# triger.net
KiCad netlist of a schematic drawn in Altium Designer
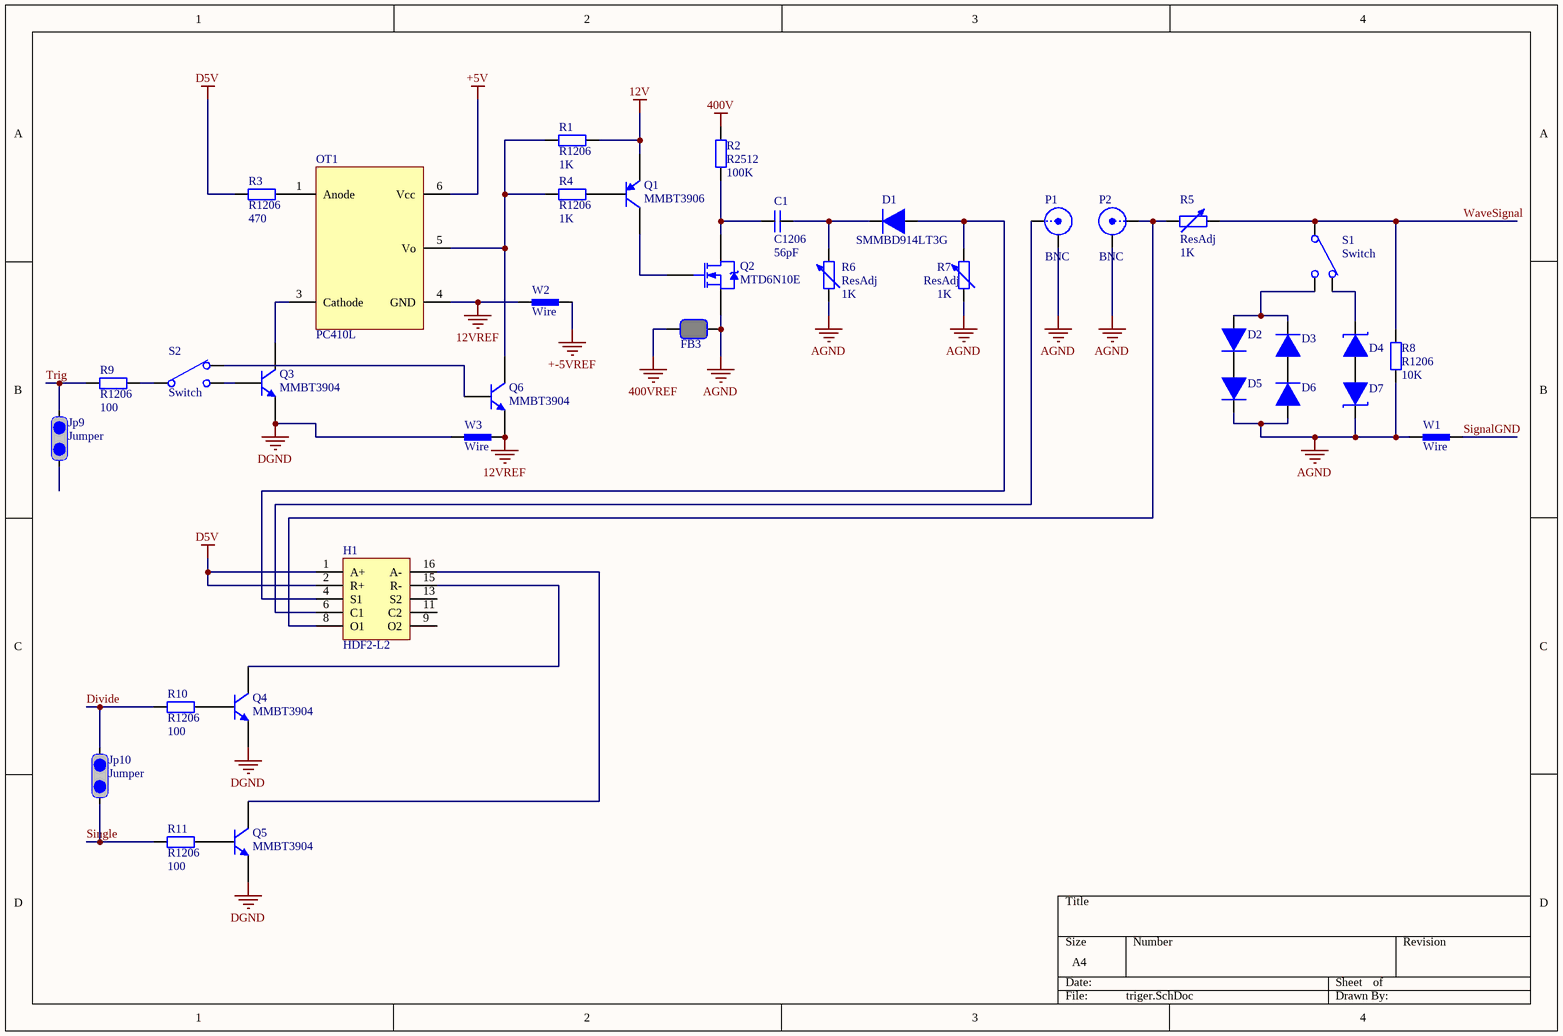
[diagram p0: triger.SchDoc]

(export (version "E")
  (design (tool "Eeschema 10.0.6"))
  (components
    (comp (ref "C1")
      (value "C1206")
      (footprint "1206")
      (description "Capacitor, 1206")
      (fields (field (name "ALTIUM_VALUE") "56pF"))
      (libsource (lib "UFDLib") (part "C1206"))
    )
    (comp (ref "D1")
      (value "SMMBD914LT3G")
      (footprint "SMMBD914LT3G")
      (description "Switching Diode")
      (libsource (lib "UFDLib") (part "SMMBD914LT3G"))
    )
    (comp (ref "D2")
      (value "SMMBD914LT3G")
      (footprint "SMMBD914LT3G")
      (description "Switching Diode")
      (libsource (lib "UFDLib") (part "SMMBD914LT3G"))
    )
    (comp (ref "D3")
      (value "SMMBD914LT3G")
      (footprint "SMMBD914LT3G")
      (description "Switching Diode")
      (libsource (lib "UFDLib") (part "SMMBD914LT3G"))
    )
    (comp (ref "D4")
      (value "ZMM2V4")
      (footprint "DIODE1206")
      (description "Voltage Stabilizing Diode, 2.4V")
      (libsource (lib "UFDLib") (part "ZMM2V4"))
    )
    (comp (ref "D5")
      (value "SMMBD914LT3G")
      (footprint "SMMBD914LT3G")
      (description "Switching Diode")
      (libsource (lib "UFDLib") (part "SMMBD914LT3G"))
    )
    (comp (ref "D6")
      (value "SMMBD914LT3G")
      (footprint "SMMBD914LT3G")
      (description "Switching Diode")
      (libsource (lib "UFDLib") (part "SMMBD914LT3G"))
    )
    (comp (ref "D7")
      (value "ZMM2V4")
      (footprint "DIODE1206")
      (description "Voltage Stabilizing Diode, 2.4V")
      (libsource (lib "UFDLib") (part "ZMM2V4"))
    )
    (comp (ref "FB3")
      (value "FB0805")
      (footprint "0805")
      (description "Chip Bead, 0805")
      (libsource (lib "UFDLib") (part "FB0805"))
    )
    (comp (ref "H1")
      (value "HDF2-L2")
      (footprint "RELAY-HFD2-L2")
      (description "Relay, HDF2-XX-XX-L2-XX")
      (libsource (lib "UFDLib") (part "Relay-HDF2-L2"))
    )
    (comp (ref "Jp9") (value "Jumper") (footprint "JUMPER") (libsource (lib "UFDLib") (part "Jumper")))
    (comp (ref "Jp10") (value "Jumper") (footprint "JUMPER") (libsource (lib "UFDLib") (part "Jumper")))
    (comp (ref "OT1") (value "PC410L") (footprint "SOP5") (libsource (lib "UFDLib") (part "PC410L")))
    (comp (ref "P1")
      (value "BNC")
      (footprint "BNC_RA CON")
      (description "BNC Elbow Connector")
      (fields (field (name "PUBLISHER") "Altium Limited"))
      (libsource (lib "Miscellaneous Connectors") (part "BNC"))
    )
    (comp (ref "P2")
      (value "BNC")
      (footprint "BNC_RA CON")
      (description "BNC Elbow Connector")
      (fields (field (name "PUBLISHER") "Altium Limited"))
      (libsource (lib "Miscellaneous Connectors") (part "BNC"))
    )
    (comp (ref "Q1")
      (value "MMBT3906")
      (footprint "SOT23_M")
      (description "PNP Switching Transistor")
      (fields (field (name "PUBLISHER") "Altium Limited"))
      (libsource (lib "Philips Discrete BJT - Low Power") (part "MMBT3906"))
    )
    (comp (ref "Q2")
      (value "MTD6N10E")
      (footprint "369A-13")
      (description "TMOS E-FET Power Field Effect Transistor DPAK for Surface Mount")
      (fields (field (name "PUBLISHER") "Altium Limited"))
      (libsource (lib "Motorola Discrete MOSFET") (part "MTD6N10E"))
    )
    (comp (ref "Q3")
      (value "MMBT3904")
      (footprint "SOT23_M")
      (description "NPN Switching Transistor")
      (fields (field (name "PUBLISHER") "Altium Limited"))
      (libsource (lib "Philips Discrete BJT - Low Power") (part "MMBT3904"))
    )
    (comp (ref "Q4")
      (value "MMBT3904")
      (footprint "SOT23_M")
      (description "NPN Switching Transistor")
      (fields (field (name "PUBLISHER") "Altium Limited"))
      (libsource (lib "Philips Discrete BJT - Low Power") (part "MMBT3904"))
    )
    (comp (ref "Q5")
      (value "MMBT3904")
      (footprint "SOT23_M")
      (description "NPN Switching Transistor")
      (fields (field (name "PUBLISHER") "Altium Limited"))
      (libsource (lib "Philips Discrete BJT - Low Power") (part "MMBT3904"))
    )
    (comp (ref "Q6")
      (value "MMBT3904")
      (footprint "SOT23_M")
      (description "NPN Switching Transistor")
      (fields (field (name "PUBLISHER") "Altium Limited"))
      (libsource (lib "Philips Discrete BJT - Low Power") (part "MMBT3904"))
    )
    (comp (ref "R1")
      (value "R1206")
      (footprint "1206")
      (description "Resistor, 1206, 1/4W")
      (fields (field (name "ALTIUM_VALUE") "1K"))
      (libsource (lib "UFDLib") (part "R1206"))
    )
    (comp (ref "R2")
      (value "R2512")
      (footprint "2512")
      (description "Resistor, 2512, 1W")
      (fields (field (name "ALTIUM_VALUE") "100K"))
      (libsource (lib "UFDLib") (part "R2512"))
    )
    (comp (ref "R3")
      (value "R1206")
      (footprint "1206")
      (description "Resistor, 1206, 1/4W")
      (fields (field (name "ALTIUM_VALUE") "470"))
      (libsource (lib "UFDLib") (part "R1206"))
    )
    (comp (ref "R4")
      (value "R1206")
      (footprint "1206")
      (description "Resistor, 1206, 1/4W")
      (fields (field (name "ALTIUM_VALUE") "1K"))
      (libsource (lib "UFDLib") (part "R1206"))
    )
    (comp (ref "R5")
      (value "ResAdj")
      (footprint "Adjust Resistor")
      (description "Adjustable Resistor")
      (fields (field (name "ALTIUM_VALUE") "1K"))
      (libsource (lib "UFDLib") (part "ResAdj"))
    )
    (comp (ref "R6")
      (value "ResAdj")
      (footprint "Adjust Resistor")
      (description "Adjustable Resistor")
      (fields (field (name "ALTIUM_VALUE") "1K"))
      (libsource (lib "") (part "ResAdj_1"))
    )
    (comp (ref "R7")
      (value "ResAdj")
      (footprint "Adjust Resistor")
      (description "Adjustable Resistor")
      (fields (field (name "ALTIUM_VALUE") "1K"))
      (libsource (lib "") (part "ResAdj_1"))
    )
    (comp (ref "R8")
      (value "R1206")
      (footprint "1206")
      (description "Resistor, 1206, 1/4W")
      (fields (field (name "ALTIUM_VALUE") "10K"))
      (libsource (lib "") (part "R1206_1"))
    )
    (comp (ref "R9")
      (value "R1206")
      (footprint "1206")
      (description "Resistor, 1206, 1/4W")
      (fields (field (name "ALTIUM_VALUE") "100"))
      (libsource (lib "UFDLib") (part "R1206"))
    )
    (comp (ref "R10")
      (value "R1206")
      (footprint "1206")
      (description "Resistor, 1206, 1/4W")
      (fields (field (name "ALTIUM_VALUE") "100"))
      (libsource (lib "UFDLib") (part "R1206"))
    )
    (comp (ref "R11")
      (value "R1206")
      (footprint "1206")
      (description "Resistor, 1206, 1/4W")
      (fields (field (name "ALTIUM_VALUE") "100"))
      (libsource (lib "UFDLib") (part "R1206"))
    )
    (comp (ref "S1")
      (value "Switch")
      (footprint "MSS-22C02")
      (description "Duble Switch")
      (libsource (lib "UFDLib") (part "MSS-22C02"))
    )
    (comp (ref "S2")
      (value "Switch")
      (footprint "MSS-22C02")
      (description "Duble Switch")
      (libsource (lib "UFDLib") (part "MSS-22C02"))
    )
    (comp (ref "W1") (value "Wire") (footprint "WIRE") (libsource (lib "UFDLib") (part "Wire")))
    (comp (ref "W2") (value "Wire") (footprint "WIRE") (libsource (lib "UFDLib") (part "Wire")))
    (comp (ref "W3") (value "Wire") (footprint "WIRE") (libsource (lib "UFDLib") (part "Wire")))
  )
  (nets
    (net (code "1") (name "+-5VREF") (class "Default")
      (node (ref "W2") (pin "2") (pinfunction "b_2") (pintype "passive"))
    )
    (net (code "2") (name "+5V") (class "Default")
      (node (ref "OT1") (pin "6") (pinfunction "Vcc_6") (pintype "passive"))
    )
    (net (code "3") (name "/Divide") (class "Default")
      (node (ref "Jp10") (pin "2") (pinfunction "b_2") (pintype "passive"))
      (node (ref "R10") (pin "1") (pinfunction "a_1") (pintype "passive"))
    )
    (net (code "4") (name "/SignalGND") (class "Default")
      (node (ref "W1") (pin "2") (pinfunction "b_2") (pintype "passive"))
    )
    (net (code "5") (name "/Single") (class "Default")
      (node (ref "Jp10") (pin "1") (pinfunction "a_1") (pintype "passive"))
      (node (ref "R11") (pin "1") (pinfunction "a_1") (pintype "passive"))
    )
    (net (code "6") (name "/Trig") (class "Default")
      (node (ref "Jp9") (pin "2") (pinfunction "b_2") (pintype "passive"))
      (node (ref "R9") (pin "1") (pinfunction "a_1") (pintype "passive"))
    )
    (net (code "7") (name "/WaveSignal") (class "Default")
      (node (ref "R5") (pin "b") (pinfunction "b_b") (pintype "passive"))
      (node (ref "R8") (pin "2") (pinfunction "b_2") (pintype "passive"))
      (node (ref "S1") (pin "a") (pinfunction "a_a") (pintype "passive"))
    )
    (net (code "8") (name "12V") (class "Default")
      (node (ref "Q1") (pin "2") (pinfunction "E_2") (pintype "passive"))
      (node (ref "R1") (pin "2") (pinfunction "b_2") (pintype "passive"))
    )
    (net (code "9") (name "12VREF") (class "Default")
      (node (ref "OT1") (pin "4") (pinfunction "GND_4") (pintype "passive"))
      (node (ref "Q6") (pin "2") (pinfunction "E_2") (pintype "passive"))
      (node (ref "W2") (pin "1") (pinfunction "a_1") (pintype "passive"))
      (node (ref "W3") (pin "2") (pinfunction "b_2") (pintype "passive"))
    )
    (net (code "10") (name "400V") (class "Default")
      (node (ref "R2") (pin "2") (pinfunction "b_2") (pintype "passive"))
    )
    (net (code "11") (name "400VREF") (class "Default")
      (node (ref "FB3") (pin "2") (pinfunction "b_2") (pintype "passive"))
    )
    (net (code "12") (name "AGND") (class "Default")
      (node (ref "D5") (pin "3") (pinfunction "c_3") (pintype "passive"))
      (node (ref "D6") (pin "1") (pinfunction "a_1") (pintype "passive"))
      (node (ref "D7") (pin "2") (pinfunction "b_2") (pintype "passive"))
      (node (ref "FB3") (pin "1") (pinfunction "a_1") (pintype "passive"))
      (node (ref "P1") (pin "2") (pinfunction "Y_2") (pintype "passive"))
      (node (ref "P2") (pin "2") (pinfunction "Y_2") (pintype "passive"))
      (node (ref "Q2") (pin "3") (pinfunction "S_3") (pintype "passive"))
      (node (ref "R6") (pin "a") (pinfunction "a_a") (pintype "passive"))
      (node (ref "R7") (pin "a") (pinfunction "a_a") (pintype "passive"))
      (node (ref "R8") (pin "1") (pinfunction "a_1") (pintype "passive"))
      (node (ref "W1") (pin "1") (pinfunction "a_1") (pintype "passive"))
    )
    (net (code "13") (name "D5V") (class "Default")
      (node (ref "H1") (pin "1") (pinfunction "A+_1") (pintype "passive"))
      (node (ref "H1") (pin "2") (pinfunction "R+_2") (pintype "passive"))
      (node (ref "R3") (pin "1") (pinfunction "a_1") (pintype "passive"))
    )
    (net (code "14") (name "DGND") (class "Default")
      (node (ref "Q3") (pin "2") (pinfunction "E_2") (pintype "passive"))
      (node (ref "Q4") (pin "2") (pinfunction "E_2") (pintype "passive"))
      (node (ref "Q5") (pin "2") (pinfunction "E_2") (pintype "passive"))
      (node (ref "W3") (pin "1") (pinfunction "a_1") (pintype "passive"))
    )
    (net (code "15") (name "Net-(C1-a)") (class "Default")
      (node (ref "C1") (pin "1") (pinfunction "a_1") (pintype "passive"))
      (node (ref "Q2") (pin "4") (pinfunction "D_4") (pintype "passive"))
      (node (ref "R2") (pin "1") (pinfunction "a_1") (pintype "passive"))
    )
    (net (code "16") (name "Net-(C1-b)") (class "Default")
      (node (ref "C1") (pin "2") (pinfunction "b_2") (pintype "passive"))
      (node (ref "D1") (pin "3") (pinfunction "c_3") (pintype "passive"))
      (node (ref "R6") (pin "b") (pinfunction "b_b") (pintype "passive"))
    )
    (net (code "17") (name "Net-(D1-a)") (class "Default")
      (node (ref "D1") (pin "1") (pinfunction "a_1") (pintype "passive"))
      (node (ref "H1") (pin "4") (pinfunction "S1_4") (pintype "passive"))
      (node (ref "R7") (pin "b") (pinfunction "b_b") (pintype "passive"))
    )
    (net (code "18") (name "Net-(D2-a)") (class "Default")
      (node (ref "D2") (pin "1") (pinfunction "a_1") (pintype "passive"))
      (node (ref "D3") (pin "3") (pinfunction "c_3") (pintype "passive"))
      (node (ref "S1") (pin "c") (pinfunction "c_c") (pintype "passive"))
    )
    (net (code "19") (name "Net-(D2-c)") (class "Default")
      (node (ref "D2") (pin "3") (pinfunction "c_3") (pintype "passive"))
      (node (ref "D5") (pin "1") (pinfunction "a_1") (pintype "passive"))
    )
    (net (code "20") (name "Net-(D3-a)") (class "Default")
      (node (ref "D3") (pin "1") (pinfunction "a_1") (pintype "passive"))
      (node (ref "D6") (pin "3") (pinfunction "c_3") (pintype "passive"))
    )
    (net (code "21") (name "Net-(D4-a)") (class "Default")
      (node (ref "D4") (pin "1") (pinfunction "a_1") (pintype "passive"))
      (node (ref "D7") (pin "1") (pinfunction "a_1") (pintype "passive"))
    )
    (net (code "22") (name "Net-(D4-b)") (class "Default")
      (node (ref "D4") (pin "2") (pinfunction "b_2") (pintype "passive"))
      (node (ref "S1") (pin "b") (pinfunction "b_b") (pintype "passive"))
    )
    (net (code "23") (name "Net-(H1-A-)") (class "Default")
      (node (ref "H1") (pin "16") (pinfunction "A-_16") (pintype "passive"))
      (node (ref "Q5") (pin "3") (pinfunction "C_3") (pintype "passive"))
    )
    (net (code "24") (name "Net-(H1-C1)") (class "Default")
      (node (ref "H1") (pin "6") (pinfunction "C1_6") (pintype "passive"))
      (node (ref "P1") (pin "1") (pinfunction "X_1") (pintype "passive"))
    )
    (net (code "25") (name "Net-(H1-O1)") (class "Default")
      (node (ref "H1") (pin "8") (pinfunction "O1_8") (pintype "passive"))
      (node (ref "P2") (pin "1") (pinfunction "X_1") (pintype "passive"))
      (node (ref "R5") (pin "a") (pinfunction "a_a") (pintype "passive"))
    )
    (net (code "26") (name "Net-(H1-R-)") (class "Default")
      (node (ref "H1") (pin "15") (pinfunction "R-_15") (pintype "passive"))
      (node (ref "Q4") (pin "3") (pinfunction "C_3") (pintype "passive"))
    )
    (net (code "27") (name "Net-(OT1-Anode)") (class "Default")
      (node (ref "OT1") (pin "1") (pinfunction "Anode_1") (pintype "passive"))
      (node (ref "R3") (pin "2") (pinfunction "b_2") (pintype "passive"))
    )
    (net (code "28") (name "Net-(OT1-Cathode)") (class "Default")
      (node (ref "OT1") (pin "3") (pinfunction "Cathode_3") (pintype "passive"))
      (node (ref "Q3") (pin "3") (pinfunction "C_3") (pintype "passive"))
    )
    (net (code "29") (name "Net-(OT1-Vo)") (class "Default")
      (node (ref "OT1") (pin "5") (pinfunction "Vo_5") (pintype "passive"))
      (node (ref "Q6") (pin "3") (pinfunction "C_3") (pintype "passive"))
      (node (ref "R1") (pin "1") (pinfunction "a_1") (pintype "passive"))
      (node (ref "R4") (pin "1") (pinfunction "a_1") (pintype "passive"))
    )
    (net (code "30") (name "Net-(Q1-B)") (class "Default")
      (node (ref "Q1") (pin "1") (pinfunction "B_1") (pintype "passive"))
      (node (ref "R4") (pin "2") (pinfunction "b_2") (pintype "passive"))
    )
    (net (code "31") (name "Net-(Q1-C)") (class "Default")
      (node (ref "Q1") (pin "3") (pinfunction "C_3") (pintype "passive"))
      (node (ref "Q2") (pin "1") (pinfunction "G_1") (pintype "passive"))
    )
    (net (code "32") (name "Net-(Q3-B)") (class "Default")
      (node (ref "Q3") (pin "1") (pinfunction "B_1") (pintype "passive"))
      (node (ref "S2") (pin "c") (pinfunction "c_c") (pintype "passive"))
    )
    (net (code "33") (name "Net-(Q4-B)") (class "Default")
      (node (ref "Q4") (pin "1") (pinfunction "B_1") (pintype "passive"))
      (node (ref "R10") (pin "2") (pinfunction "b_2") (pintype "passive"))
    )
    (net (code "34") (name "Net-(Q5-B)") (class "Default")
      (node (ref "Q5") (pin "1") (pinfunction "B_1") (pintype "passive"))
      (node (ref "R11") (pin "2") (pinfunction "b_2") (pintype "passive"))
    )
    (net (code "35") (name "Net-(Q6-B)") (class "Default")
      (node (ref "Q6") (pin "1") (pinfunction "B_1") (pintype "passive"))
      (node (ref "S2") (pin "b") (pinfunction "b_b") (pintype "passive"))
    )
    (net (code "36") (name "Net-(R9-b)") (class "Default")
      (node (ref "R9") (pin "2") (pinfunction "b_2") (pintype "passive"))
      (node (ref "S2") (pin "a") (pinfunction "a_a") (pintype "passive"))
    )
    (net (code "37") (name "unconnected-(H1-C2-Pad11)") (class "Default")
      (node (ref "H1") (pin "11") (pinfunction "C2_11") (pintype "passive"))
    )
    (net (code "38") (name "unconnected-(H1-O2-Pad9)") (class "Default")
      (node (ref "H1") (pin "9") (pinfunction "O2_9") (pintype "passive"))
    )
    (net (code "39") (name "unconnected-(H1-S2-Pad13)") (class "Default")
      (node (ref "H1") (pin "13") (pinfunction "S2_13") (pintype "passive"))
    )
    (net (code "40") (name "unconnected-(Jp9-a-Pad1)") (class "Default")
      (node (ref "Jp9") (pin "1") (pinfunction "a_1") (pintype "passive"))
    )
  )
)
